# controller.net
KiCad netlist of a schematic drawn in EAGLE
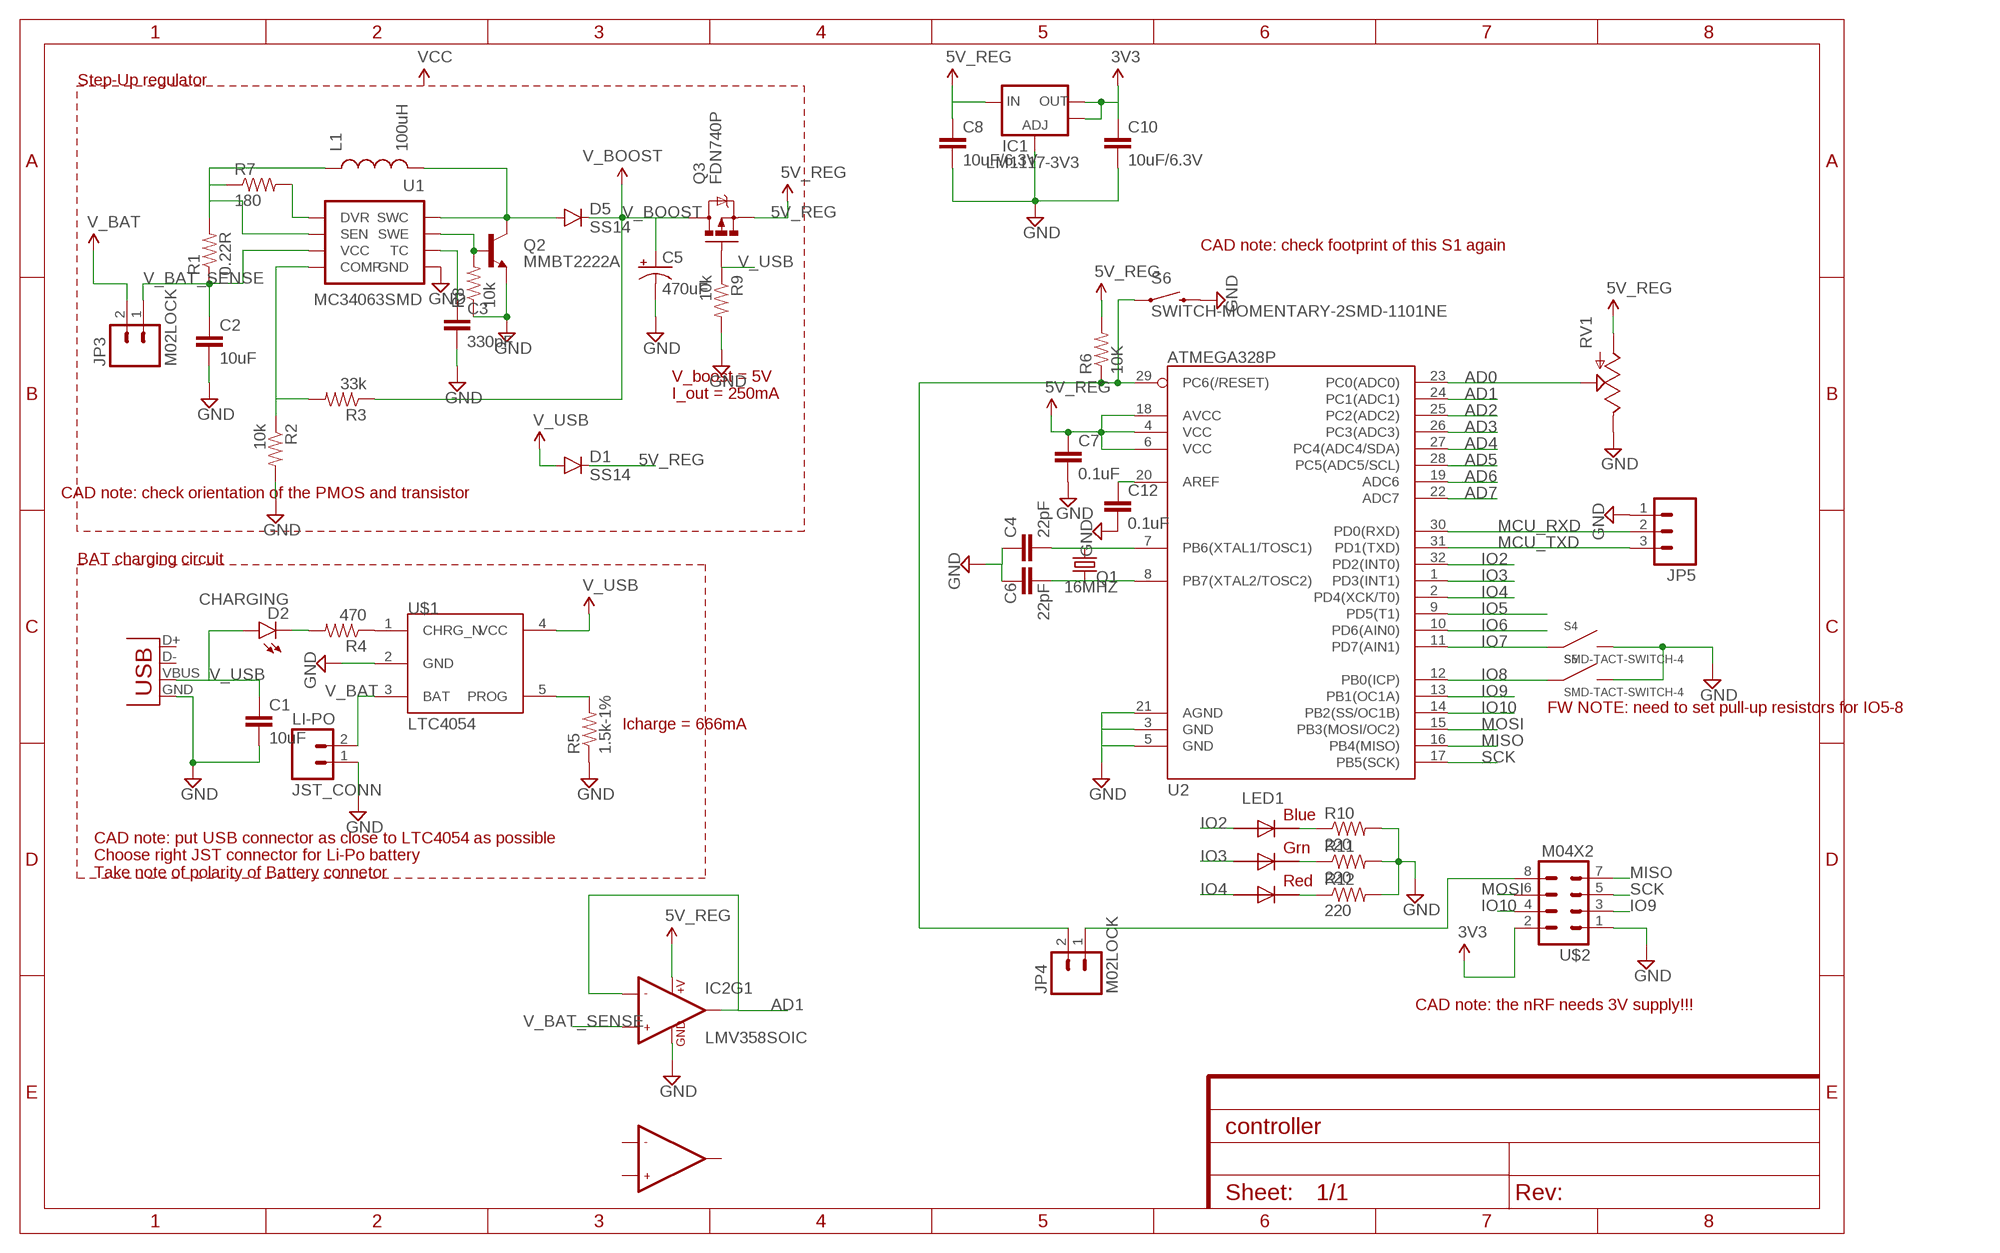
[diagram p0: schematic, sheet 1]

(export (version "E")
  (design (tool "Eeschema 10.0.6"))
  (components
    (comp (ref "C1")
      (value "10uF")
      (footprint "eagle-import:0603-CAP")
      (libsource (lib "eagle-import") (part "1.0UF-16V-10%(0603)"))
    )
    (comp (ref "C2")
      (value "10uF")
      (footprint "eagle-import:0603-CAP")
      (libsource (lib "eagle-import") (part "10UF-6.3V-20%(0603)"))
    )
    (comp (ref "C3")
      (value "330pF")
      (footprint "eagle-import:0805")
      (libsource (lib "eagle-import") (part "1.0UF-25V-+80/-20(0805)"))
    )
    (comp (ref "C4")
      (value "22pF")
      (footprint "eagle-import:0603-CAP")
      (libsource (lib "eagle-import") (part "22PF-50V-5%(0603)"))
    )
    (comp (ref "C5")
      (value "470uF")
      (footprint "eagle-import:EIA7343")
      (libsource (lib "eagle-import") (part "100UF-10V-10%(TANT)"))
    )
    (comp (ref "C6")
      (value "22pF")
      (footprint "eagle-import:0603-CAP")
      (libsource (lib "eagle-import") (part "22PF-50V-5%(0603)"))
    )
    (comp (ref "C7")
      (value "0.1uF")
      (footprint "eagle-import:0603-CAP")
      (libsource (lib "eagle-import") (part "0.1UF-25V(+80/-20%)(0603)"))
    )
    (comp (ref "C8")
      (value "10uF/6.3V")
      (footprint "eagle-import:0603-CAP")
      (libsource (lib "eagle-import") (part "10UF-6.3V-20%(0603)"))
    )
    (comp (ref "C10")
      (value "10uF/6.3V")
      (footprint "eagle-import:0603-CAP")
      (libsource (lib "eagle-import") (part "10UF-6.3V-20%(0603)"))
    )
    (comp (ref "C12")
      (value "0.1uF")
      (footprint "eagle-import:0603-CAP")
      (libsource (lib "eagle-import") (part "0.1UF-25V(+80/-20%)(0603)"))
    )
    (comp (ref "D1")
      (value "SS14")
      (footprint "eagle-import:SMA-DIODE_ALT")
      (libsource (lib "eagle-import") (part "DIODESMA-ALT"))
    )
    (comp (ref "D2")
      (value "CHARGING")
      (footprint "eagle-import:LED-0603")
      (libsource (lib "eagle-import") (part "LED-GREEN0603"))
    )
    (comp (ref "D5")
      (value "SS14")
      (footprint "eagle-import:SMA-DIODE_ALT")
      (libsource (lib "eagle-import") (part "DIODESMA-ALT"))
    )
    (comp (ref "IC1")
      (value "LM1117-3V3")
      (footprint "eagle-import:SOT223")
      (libsource (lib "eagle-import") (part "V_REG_LM1117SOT223"))
    )
    (comp (ref "IC2")
      (value "LMV358SOIC")
      (footprint "eagle-import:SO08")
      (libsource (lib "eagle-import") (part "LMV358SOIC"))
    )
    (comp (ref "JP1")
      (value "USB-SMD-NS")
      (footprint "eagle-import:USB-MINIB-NOSTOP")
      (libsource (lib "eagle-import") (part "USB-SMD-NS"))
    )
    (comp (ref "JP3")
      (value "M02LOCK")
      (footprint "eagle-import:1X02_LOCK")
      (libsource (lib "eagle-import") (part "M02LOCK"))
    )
    (comp (ref "JP4")
      (value "M02LOCK")
      (footprint "eagle-import:1X02_LOCK")
      (libsource (lib "eagle-import") (part "M02LOCK"))
    )
    (comp (ref "JP5")
      (value "M03LOCK")
      (footprint "eagle-import:1X03_LOCK")
      (libsource (lib "eagle-import") (part "M03LOCK"))
    )
    (comp (ref "L1")
      (value "100uH")
      (footprint "eagle-import:SRN6045")
      (libsource (lib "eagle-import") (part "INDUCTORBOURNS_SRN6045"))
    )
    (comp (ref "LED1")
      (value "RGBLED5050")
      (footprint "eagle-import:RGBLED5050")
      (libsource (lib "eagle-import") (part "RGBLED5050"))
    )
    (comp (ref "LI-PO")
      (value "JST_CONN")
      (footprint "eagle-import:JST-2-PTH-VERT")
      (libsource (lib "eagle-import") (part "M02JST-PTH-VERT"))
    )
    (comp (ref "Q1")
      (value "16MHZ")
      (footprint "eagle-import:HC49_S")
      (libsource (lib "eagle-import") (part "CRYSTALHC49S"))
    )
    (comp (ref "Q2")
      (value "MMBT2222A")
      (footprint "eagle-import:SOT23-3")
      (libsource (lib "eagle-import") (part "TRANSISTOR_NPNMMBT2222A"))
    )
    (comp (ref "Q3")
      (value "FDN740P")
      (footprint "eagle-import:SOT23-3")
      (libsource (lib "eagle-import") (part "MOSFET-PCHANNEL"))
    )
    (comp (ref "R1")
      (value "0.22R")
      (footprint "eagle-import:0805")
      (libsource (lib "eagle-import") (part "0.22OHM-1/4W-1%(0805)"))
    )
    (comp (ref "R2")
      (value "10k")
      (footprint "eagle-import:0603-RES")
      (libsource (lib "eagle-import") (part "1KOHM-1/10W-1%(0603)"))
    )
    (comp (ref "R3")
      (value "33k")
      (footprint "eagle-import:0603-RES")
      (libsource (lib "eagle-import") (part "1KOHM-1/10W-1%(0603)"))
    )
    (comp (ref "R4")
      (value "470")
      (footprint "eagle-import:0603-RES")
      (libsource (lib "eagle-import") (part "470OHM1/10W1%(0603)"))
    )
    (comp (ref "R5")
      (value "1.5k-1%")
      (footprint "eagle-import:0805")
      (libsource (lib "eagle-import") (part "0.22OHM-1/4W-1%(0805)"))
    )
    (comp (ref "R6")
      (value "10K")
      (footprint "eagle-import:0603-RES")
      (libsource (lib "eagle-import") (part "10KOHM-1/10W-1%(0603)0603"))
    )
    (comp (ref "R7")
      (value "180")
      (footprint "eagle-import:0603-RES")
      (libsource (lib "eagle-import") (part "RESISTOR0603"))
    )
    (comp (ref "R8")
      (value "10k")
      (footprint "eagle-import:0603-RES")
      (libsource (lib "eagle-import") (part "RESISTOR0603"))
    )
    (comp (ref "R9")
      (value "10k")
      (footprint "eagle-import:0603-RES")
      (libsource (lib "eagle-import") (part "RESISTOR0603"))
    )
    (comp (ref "R10")
      (value "220")
      (footprint "eagle-import:0603-RES")
      (libsource (lib "eagle-import") (part "RESISTOR0603"))
    )
    (comp (ref "R11")
      (value "220")
      (footprint "eagle-import:0603-RES")
      (libsource (lib "eagle-import") (part "RESISTOR0603"))
    )
    (comp (ref "R12")
      (value "220")
      (footprint "eagle-import:0603-RES")
      (libsource (lib "eagle-import") (part "RESISTOR0603"))
    )
    (comp (ref "RV1")
      (value "POT-RV16AF-20")
      (footprint "eagle-import:POT_ALPHA_RV16AF-20")
      (libsource (lib "eagle-import") (part "POT-RV16AF-20"))
    )
    (comp (ref "S4")
      (value "SMD-TACT-SWITCH-4")
      (footprint "eagle-import:SMD-TACTSWITCH-6X6X3")
      (libsource (lib "eagle-import") (part "SMD-TACT-SWITCH-4"))
    )
    (comp (ref "S5")
      (value "SMD-TACT-SWITCH-4")
      (footprint "eagle-import:SMD-TACTSWITCH-6X6X3")
      (libsource (lib "eagle-import") (part "SMD-TACT-SWITCH-4"))
    )
    (comp (ref "S6")
      (value "SWITCH-MOMENTARY-2SMD-1101NE")
      (footprint "eagle-import:TACTILE-SWITCH-1101NE")
      (libsource (lib "eagle-import") (part "SWITCH-MOMENTARY-2SMD-1101NE"))
    )
    (comp (ref "U$1")
      (value "LTC4054")
      (footprint "eagle-import:SOT23-5")
      (libsource (lib "eagle-import") (part "LTC4054"))
    )
    (comp (ref "U$2")
      (value "M04X2")
      (footprint "eagle-import:2X4")
      (libsource (lib "eagle-import") (part "M04X2"))
    )
    (comp (ref "U1")
      (value "MC34063SMD")
      (footprint "eagle-import:SO08")
      (libsource (lib "eagle-import") (part "MC34063SMD"))
    )
    (comp (ref "U2")
      (value "ATMEGA328P")
      (footprint "eagle-import:TQFP32-08")
      (libsource (lib "eagle-import") (part "ATMEGA328_SMT"))
    )
  )
  (nets
    (net (code "1") (name "/AD0") (class "Default")
      (node (ref "RV1") (pin "2") (pinfunction "S_2") (pintype "passive"))
      (node (ref "U2") (pin "23") (pinfunction "PC0(ADC0)_23") (pintype "bidirectional"))
    )
    (net (code "2") (name "/AD1") (class "Default")
      (node (ref "IC2") (pin "1") (pinfunction "OUT1_1") (pintype "output"))
      (node (ref "IC2") (pin "2") (pinfunction "-IN1_2") (pintype "input"))
      (node (ref "U2") (pin "24") (pinfunction "PC1(ADC1)_24") (pintype "bidirectional"))
    )
    (net (code "3") (name "/AD2") (class "Default")
      (node (ref "U2") (pin "25") (pinfunction "PC2(ADC2)_25") (pintype "bidirectional"))
    )
    (net (code "4") (name "/AD3") (class "Default")
      (node (ref "U2") (pin "26") (pinfunction "PC3(ADC3)_26") (pintype "bidirectional"))
    )
    (net (code "5") (name "/AD4") (class "Default")
      (node (ref "U2") (pin "27") (pinfunction "PC4(ADC4/SDA)_27") (pintype "bidirectional"))
    )
    (net (code "6") (name "/AD5") (class "Default")
      (node (ref "U2") (pin "28") (pinfunction "PC5(ADC5/SCL)_28") (pintype "bidirectional"))
    )
    (net (code "7") (name "/AD6") (class "Default")
      (node (ref "U2") (pin "19") (pinfunction "ADC6_19") (pintype "bidirectional"))
    )
    (net (code "8") (name "/AD7") (class "Default")
      (node (ref "U2") (pin "22") (pinfunction "ADC7_22") (pintype "bidirectional"))
    )
    (net (code "9") (name "/IO2") (class "Default")
      (node (ref "LED1") (pin "3") (pinfunction "BLUE_A_3") (pintype "bidirectional"))
      (node (ref "U2") (pin "32") (pinfunction "PD2(INT0)_32") (pintype "bidirectional"))
    )
    (net (code "10") (name "/IO3") (class "Default")
      (node (ref "LED1") (pin "1") (pinfunction "GREEN_A_1") (pintype "bidirectional"))
      (node (ref "U2") (pin "1") (pinfunction "PD3(INT1)_1") (pintype "bidirectional"))
    )
    (net (code "11") (name "/IO4") (class "Default")
      (node (ref "LED1") (pin "2") (pinfunction "RED_A_2") (pintype "bidirectional"))
      (node (ref "U2") (pin "2") (pinfunction "PD4(XCK/T0)_2") (pintype "bidirectional"))
    )
    (net (code "12") (name "/IO5") (class "Default")
      (node (ref "U2") (pin "9") (pinfunction "PD5(T1)_9") (pintype "bidirectional"))
    )
    (net (code "13") (name "/IO6") (class "Default")
      (node (ref "U2") (pin "10") (pinfunction "PD6(AIN0)_10") (pintype "bidirectional"))
    )
    (net (code "14") (name "/IO7") (class "Default")
      (node (ref "S4") (pin "P$1") (pinfunction "P$1_P$1") (pintype "bidirectional"))
      (node (ref "U2") (pin "11") (pinfunction "PD7(AIN1)_11") (pintype "bidirectional"))
    )
    (net (code "15") (name "/IO8") (class "Default")
      (node (ref "S5") (pin "P$1") (pinfunction "P$1_P$1") (pintype "bidirectional"))
      (node (ref "U2") (pin "12") (pinfunction "PB0(ICP)_12") (pintype "bidirectional"))
    )
    (net (code "16") (name "/IO9") (class "Default")
      (node (ref "U$2") (pin "3") (pinfunction "3_3") (pintype "passive"))
      (node (ref "U2") (pin "13") (pinfunction "PB1(OC1A)_13") (pintype "bidirectional"))
    )
    (net (code "17") (name "/IO10") (class "Default")
      (node (ref "U$2") (pin "4") (pinfunction "4_4") (pintype "passive"))
      (node (ref "U2") (pin "14") (pinfunction "PB2(SS/OC1B)_14") (pintype "bidirectional"))
    )
    (net (code "18") (name "/MCU_RXD") (class "Default")
      (node (ref "JP5") (pin "2") (pinfunction "2_2") (pintype "passive"))
      (node (ref "U2") (pin "30") (pinfunction "PD0(RXD)_30") (pintype "bidirectional"))
    )
    (net (code "19") (name "/MCU_TXD") (class "Default")
      (node (ref "JP5") (pin "3") (pinfunction "3_3") (pintype "passive"))
      (node (ref "U2") (pin "31") (pinfunction "PD1(TXD)_31") (pintype "bidirectional"))
    )
    (net (code "20") (name "/MISO") (class "Default")
      (node (ref "U$2") (pin "7") (pinfunction "7_7") (pintype "passive"))
      (node (ref "U2") (pin "16") (pinfunction "PB4(MISO)_16") (pintype "bidirectional"))
    )
    (net (code "21") (name "/MOSI") (class "Default")
      (node (ref "U$2") (pin "6") (pinfunction "6_6") (pintype "passive"))
      (node (ref "U2") (pin "15") (pinfunction "PB3(MOSI/OC2)_15") (pintype "bidirectional"))
    )
    (net (code "22") (name "/SCK") (class "Default")
      (node (ref "U$2") (pin "5") (pinfunction "5_5") (pintype "passive"))
      (node (ref "U2") (pin "17") (pinfunction "PB5(SCK)_17") (pintype "bidirectional"))
    )
    (net (code "23") (name "/V_BAT_SENSE") (class "Default")
      (node (ref "C2") (pin "1") (pinfunction "1_1") (pintype "passive"))
      (node (ref "IC2") (pin "3") (pinfunction "+IN1_3") (pintype "input"))
      (node (ref "JP3") (pin "1") (pinfunction "1_1") (pintype "passive"))
      (node (ref "R1") (pin "1") (pinfunction "1_1") (pintype "passive"))
      (node (ref "U1") (pin "6") (pinfunction "VCC_6") (pintype "bidirectional"))
    )
    (net (code "24") (name "3V3") (class "Default")
      (node (ref "C10") (pin "1") (pinfunction "1_1") (pintype "passive"))
      (node (ref "IC1") (pin "2") (pinfunction "OUT_2") (pintype "output"))
      (node (ref "IC1") (pin "4") (pinfunction "OUT_4") (pintype "output"))
      (node (ref "U$2") (pin "2") (pinfunction "2_2") (pintype "passive"))
    )
    (net (code "25") (name "5V_REG") (class "Default")
      (node (ref "C7") (pin "1") (pinfunction "1_1") (pintype "passive"))
      (node (ref "C8") (pin "1") (pinfunction "1_1") (pintype "passive"))
      (node (ref "D1") (pin "C") (pinfunction "C_C") (pintype "passive"))
      (node (ref "IC1") (pin "3") (pinfunction "IN_3") (pintype "input"))
      (node (ref "IC2") (pin "8") (pinfunction "+V_8") (pintype "power_in"))
      (node (ref "Q3") (pin "2") (pinfunction "S_2") (pintype "passive"))
      (node (ref "R6") (pin "2") (pinfunction "2_2") (pintype "passive"))
      (node (ref "RV1") (pin "1") (pinfunction "A_1") (pintype "passive"))
      (node (ref "U2") (pin "18") (pinfunction "AVCC_18") (pintype "bidirectional"))
      (node (ref "U2") (pin "4") (pinfunction "VCC_4") (pintype "bidirectional"))
      (node (ref "U2") (pin "6") (pinfunction "VCC_6") (pintype "bidirectional"))
    )
    (net (code "26") (name "GND") (class "Default")
      (node (ref "C1") (pin "2") (pinfunction "2_2") (pintype "passive"))
      (node (ref "C10") (pin "2") (pinfunction "2_2") (pintype "passive"))
      (node (ref "C12") (pin "2") (pinfunction "2_2") (pintype "passive"))
      (node (ref "C2") (pin "2") (pinfunction "2_2") (pintype "passive"))
      (node (ref "C3") (pin "2") (pinfunction "2_2") (pintype "passive"))
      (node (ref "C4") (pin "1") (pinfunction "1_1") (pintype "passive"))
      (node (ref "C5") (pin "C") (pinfunction "-_C") (pintype "passive"))
      (node (ref "C6") (pin "1") (pinfunction "1_1") (pintype "passive"))
      (node (ref "C7") (pin "2") (pinfunction "2_2") (pintype "passive"))
      (node (ref "C8") (pin "2") (pinfunction "2_2") (pintype "passive"))
      (node (ref "IC1") (pin "1") (pinfunction "ADJ_1") (pintype "input"))
      (node (ref "IC2") (pin "4") (pinfunction "GND_4") (pintype "power_in"))
      (node (ref "JP1") (pin "GND") (pinfunction "GND_GND") (pintype "bidirectional"))
      (node (ref "JP5") (pin "1") (pinfunction "1_1") (pintype "passive"))
      (node (ref "LI-PO") (pin "1") (pinfunction "1_1") (pintype "passive"))
      (node (ref "Q2") (pin "2") (pinfunction "E_2") (pintype "passive"))
      (node (ref "R10") (pin "2") (pinfunction "2_2") (pintype "passive"))
      (node (ref "R11") (pin "2") (pinfunction "2_2") (pintype "passive"))
      (node (ref "R12") (pin "2") (pinfunction "2_2") (pintype "passive"))
      (node (ref "R2") (pin "2") (pinfunction "2_2") (pintype "passive"))
      (node (ref "R5") (pin "1") (pinfunction "1_1") (pintype "passive"))
      (node (ref "R8") (pin "1") (pinfunction "1_1") (pintype "passive"))
      (node (ref "R9") (pin "2") (pinfunction "2_2") (pintype "passive"))
      (node (ref "RV1") (pin "3") (pinfunction "E_3") (pintype "passive"))
      (node (ref "S4") (pin "P$2") (pinfunction "P$2_P$2") (pintype "bidirectional"))
      (node (ref "S5") (pin "P$2") (pinfunction "P$2_P$2") (pintype "bidirectional"))
      (node (ref "S6") (pin "2") (pinfunction "2_2") (pintype "passive"))
      (node (ref "U$1") (pin "2") (pinfunction "GND_2") (pintype "bidirectional"))
      (node (ref "U$2") (pin "1") (pinfunction "1_1") (pintype "passive"))
      (node (ref "U1") (pin "4") (pinfunction "GND_4") (pintype "bidirectional"))
      (node (ref "U2") (pin "21") (pinfunction "AGND_21") (pintype "bidirectional"))
      (node (ref "U2") (pin "3") (pinfunction "GND_3") (pintype "bidirectional"))
      (node (ref "U2") (pin "5") (pinfunction "GND_5") (pintype "bidirectional"))
    )
    (net (code "27") (name "Net-(D2-PadC)") (class "Default")
      (node (ref "D2") (pin "C") (pinfunction "C_C") (pintype "passive"))
      (node (ref "R4") (pin "2") (pinfunction "2_2") (pintype "passive"))
    )
    (net (code "28") (name "Net-(JP4-Pad1)") (class "Default")
      (node (ref "JP4") (pin "1") (pinfunction "1_1") (pintype "passive"))
      (node (ref "U$2") (pin "8") (pinfunction "8_8") (pintype "passive"))
    )
    (net (code "29") (name "Net-(LED1-BLUE_C)") (class "Default")
      (node (ref "LED1") (pin "4") (pinfunction "BLUE_C_4") (pintype "bidirectional"))
      (node (ref "R10") (pin "1") (pinfunction "1_1") (pintype "passive"))
    )
    (net (code "30") (name "Net-(LED1-GREEN_C)") (class "Default")
      (node (ref "LED1") (pin "6") (pinfunction "GREEN_C_6") (pintype "bidirectional"))
      (node (ref "R11") (pin "1") (pinfunction "1_1") (pintype "passive"))
    )
    (net (code "31") (name "Net-(LED1-RED_C)") (class "Default")
      (node (ref "LED1") (pin "5") (pinfunction "RED_C_5") (pintype "bidirectional"))
      (node (ref "R12") (pin "1") (pinfunction "1_1") (pintype "passive"))
    )
    (net (code "32") (name "Net-(Q2-B)") (class "Default")
      (node (ref "Q2") (pin "1") (pinfunction "B_1") (pintype "passive"))
      (node (ref "R8") (pin "2") (pinfunction "2_2") (pintype "passive"))
      (node (ref "U1") (pin "2") (pinfunction "SWE_2") (pintype "bidirectional"))
    )
    (net (code "33") (name "Net-(Q2-C)") (class "Default")
      (node (ref "D5") (pin "A") (pinfunction "A_A") (pintype "passive"))
      (node (ref "L1") (pin "2") (pinfunction "2_2") (pintype "passive"))
      (node (ref "Q2") (pin "3") (pinfunction "C_3") (pintype "passive"))
      (node (ref "U1") (pin "1") (pinfunction "SWC_1") (pintype "bidirectional"))
    )
    (net (code "34") (name "Net-(U$1-CHRG_N)") (class "Default")
      (node (ref "R4") (pin "1") (pinfunction "1_1") (pintype "passive"))
      (node (ref "U$1") (pin "1") (pinfunction "CHRG_N_1") (pintype "bidirectional"))
    )
    (net (code "35") (name "Net-(U$1-PROG)") (class "Default")
      (node (ref "R5") (pin "2") (pinfunction "2_2") (pintype "passive"))
      (node (ref "U$1") (pin "5") (pinfunction "PROG_5") (pintype "bidirectional"))
    )
    (net (code "36") (name "Net-(U1-COMP)") (class "Default")
      (node (ref "R2") (pin "1") (pinfunction "1_1") (pintype "passive"))
      (node (ref "R3") (pin "2") (pinfunction "2_2") (pintype "passive"))
      (node (ref "U1") (pin "5") (pinfunction "COMP_5") (pintype "bidirectional"))
    )
    (net (code "37") (name "Net-(U1-DVR)") (class "Default")
      (node (ref "R7") (pin "2") (pinfunction "2_2") (pintype "passive"))
      (node (ref "U1") (pin "8") (pinfunction "DVR_8") (pintype "bidirectional"))
    )
    (net (code "38") (name "Net-(U1-SEN)") (class "Default")
      (node (ref "L1") (pin "1") (pinfunction "1_1") (pintype "passive"))
      (node (ref "R1") (pin "2") (pinfunction "2_2") (pintype "passive"))
      (node (ref "R7") (pin "1") (pinfunction "1_1") (pintype "passive"))
      (node (ref "U1") (pin "7") (pinfunction "SEN_7") (pintype "bidirectional"))
    )
    (net (code "39") (name "Net-(U1-TC)") (class "Default")
      (node (ref "C3") (pin "1") (pinfunction "1_1") (pintype "passive"))
      (node (ref "U1") (pin "3") (pinfunction "TC_3") (pintype "bidirectional"))
    )
    (net (code "40") (name "Net-(U2-AREF)") (class "Default")
      (node (ref "C12") (pin "1") (pinfunction "1_1") (pintype "passive"))
      (node (ref "U2") (pin "20") (pinfunction "AREF_20") (pintype "bidirectional"))
    )
    (net (code "41") (name "Net-(U2-PB6(XTAL1{slash}TOSC1))") (class "Default")
      (node (ref "C4") (pin "2") (pinfunction "2_2") (pintype "passive"))
      (node (ref "Q1") (pin "2") (pinfunction "2_2") (pintype "passive"))
      (node (ref "U2") (pin "7") (pinfunction "PB6(XTAL1/TOSC1)_7") (pintype "bidirectional"))
    )
    (net (code "42") (name "Net-(U2-PB7(XTAL2{slash}TOSC2))") (class "Default")
      (node (ref "C6") (pin "2") (pinfunction "2_2") (pintype "passive"))
      (node (ref "Q1") (pin "1") (pinfunction "1_1") (pintype "passive"))
      (node (ref "U2") (pin "8") (pinfunction "PB7(XTAL2/TOSC2)_8") (pintype "bidirectional"))
    )
    (net (code "43") (name "Net-(U2-PC6({slash}RESET))") (class "Default")
      (node (ref "JP4") (pin "2") (pinfunction "2_2") (pintype "passive"))
      (node (ref "R6") (pin "1") (pinfunction "1_1") (pintype "passive"))
      (node (ref "S6") (pin "1") (pinfunction "1_1") (pintype "passive"))
      (node (ref "U2") (pin "29") (pinfunction "PC6(/RESET)_29") (pintype "bidirectional"))
    )
    (net (code "45") (name "V_BAT") (class "Default")
      (node (ref "JP3") (pin "2") (pinfunction "2_2") (pintype "passive"))
      (node (ref "LI-PO") (pin "2") (pinfunction "2_2") (pintype "passive"))
      (node (ref "U$1") (pin "3") (pinfunction "BAT_3") (pintype "bidirectional"))
    )
    (net (code "46") (name "V_BOOST") (class "Default")
      (node (ref "C5") (pin "A") (pinfunction "+_A") (pintype "passive"))
      (node (ref "D5") (pin "C") (pinfunction "C_C") (pintype "passive"))
      (node (ref "Q3") (pin "3") (pinfunction "D_3") (pintype "passive"))
      (node (ref "R3") (pin "1") (pinfunction "1_1") (pintype "passive"))
    )
    (net (code "47") (name "V_USB") (class "Default")
      (node (ref "C1") (pin "1") (pinfunction "1_1") (pintype "passive"))
      (node (ref "D1") (pin "A") (pinfunction "A_A") (pintype "passive"))
      (node (ref "D2") (pin "A") (pinfunction "A_A") (pintype "passive"))
      (node (ref "JP1") (pin "VBUS") (pinfunction "VBUS_VBUS") (pintype "bidirectional"))
      (node (ref "Q3") (pin "1") (pinfunction "G_1") (pintype "passive"))
      (node (ref "R9") (pin "1") (pinfunction "1_1") (pintype "passive"))
      (node (ref "U$1") (pin "4") (pinfunction "VCC_4") (pintype "bidirectional"))
    )
    (net (code "48") (name "unconnected-(IC2B-+IN2-Pad5)") (class "Default")
      (node (ref "IC2") (pin "5") (pinfunction "+IN2_5") (pintype "input"))
    )
    (net (code "49") (name "unconnected-(IC2B--IN2-Pad6)") (class "Default")
      (node (ref "IC2") (pin "6") (pinfunction "-IN2_6") (pintype "input"))
    )
    (net (code "50") (name "unconnected-(IC2B-OUT2-Pad7)") (class "Default")
      (node (ref "IC2") (pin "7") (pinfunction "OUT2_7") (pintype "output"))
    )
    (net (code "51") (name "unconnected-(JP1-PadD+)") (class "Default")
      (node (ref "JP1") (pin "D+") (pinfunction "D+_D+") (pintype "bidirectional"))
    )
    (net (code "52") (name "unconnected-(JP1-PadD-)") (class "Default")
      (node (ref "JP1") (pin "D-") (pinfunction "D-_D-") (pintype "bidirectional"))
    )
  )
)
